# Mechanical.net
KiCad netlist of a schematic drawn in Altium Designer
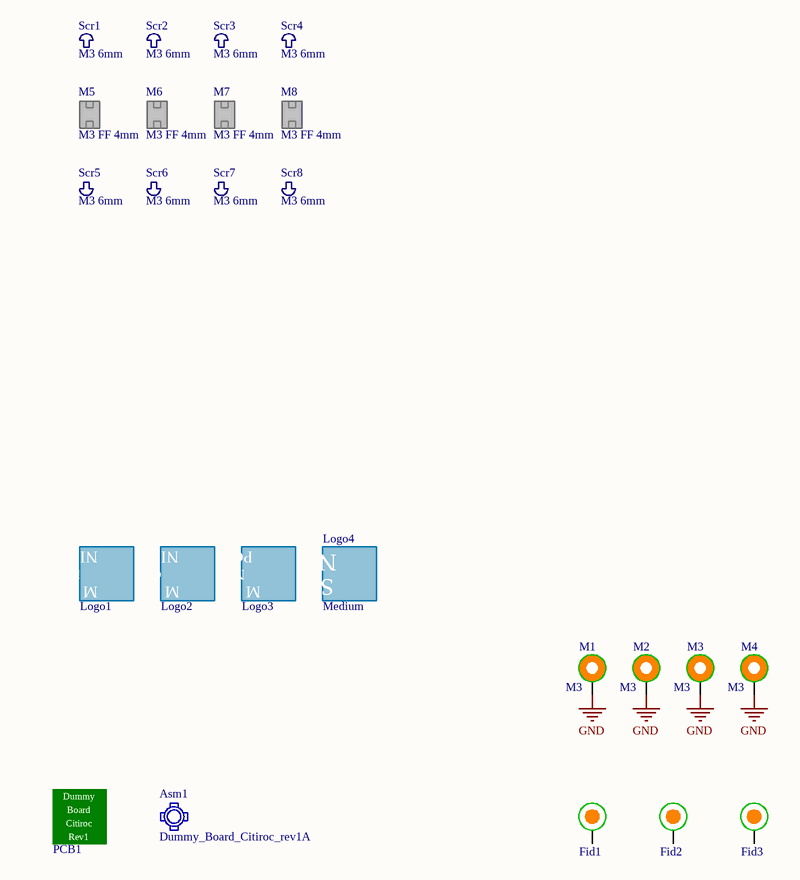
[diagram p0: Mechanical.SchDoc]

(export (version "E")
  (design (tool "Eeschema 10.0.6"))
  (components
    (comp (ref "Asm1")
      (value "Dummy_Board_Citiroc_rev1A")
      (description "Assembly_Dummy_Board_Citiroc_rev1A")
      (libsource (lib "altium-import") (part "root_0_Assembly_Dummy_Board_Citiroc_rev1A_"))
    )
    (comp (ref "Fid1")
      (value "PCB_Fiducial_Round_1mm")
      (footprint "PCB_Fiducial_Round_1mm")
      (libsource (lib "altium-import") (part "root_0_PCB_Fiducial_Round_1mm_"))
    )
    (comp (ref "Fid2")
      (value "PCB_Fiducial_Round_1mm")
      (footprint "PCB_Fiducial_Round_1mm")
      (libsource (lib "altium-import") (part "root_0_PCB_Fiducial_Round_1mm_"))
    )
    (comp (ref "Fid3")
      (value "PCB_Fiducial_Round_1mm")
      (footprint "PCB_Fiducial_Round_1mm")
      (libsource (lib "altium-import") (part "root_0_PCB_Fiducial_Round_1mm_"))
    )
    (comp (ref "Logo1")
      (value "~")
      (footprint "NI_ProjectName_M_Serigraphy")
      (description "NI_ProjectName_M_Serigraphy")
      (libsource (lib "altium-import") (part "root_0_NI_ProjectName_M_Serigraphy_"))
    )
    (comp (ref "Logo2")
      (value "NI_COMPLETE_M_LOGO")
      (footprint "NI_COMPLETE_M_LOGO")
      (libsource (lib "altium-import") (part "root_0_NI_COMPLETE_M_LOGO_"))
    )
    (comp (ref "Logo3")
      (value "PCB_Number_M")
      (footprint "NI_PCB_Number_M_Serigraphy")
      (description "NI_PCB_Number_M_Serigraphy")
      (libsource (lib "altium-import") (part "root_0_NI_PCB_Number_M_Serigraphy_"))
    )
    (comp (ref "Logo4")
      (value "Medium")
      (footprint "NI_SN_MEDIUM")
      (description "NI_SN_MEDIUM")
      (libsource (lib "altium-import") (part "root_0_NI_SN_MEDIUM_"))
    )
    (comp (ref "M1")
      (value "M3")
      (footprint "PCBPad_M3_Head6mm")
      (libsource (lib "altium-import") (part "root_0_PCBPad_M3_Head6mm_"))
    )
    (comp (ref "M2")
      (value "M3")
      (footprint "PCBPad_M3_Head6mm")
      (libsource (lib "altium-import") (part "root_0_PCBPad_M3_Head6mm_"))
    )
    (comp (ref "M3")
      (value "M3")
      (footprint "PCBPad_M3_Head6mm")
      (libsource (lib "altium-import") (part "root_0_PCBPad_M3_Head6mm_"))
    )
    (comp (ref "M4")
      (value "M3")
      (footprint "PCBPad_M3_Head6mm")
      (libsource (lib "altium-import") (part "root_0_PCBPad_M3_Head6mm_"))
    )
    (comp (ref "M5")
      (value "M3 FF 4mm")
      (libsource (lib "altium-import") (part "root_0_Hex_Spacer_R30_M3_FF_4mm_"))
    )
    (comp (ref "M6")
      (value "M3 FF 4mm")
      (libsource (lib "altium-import") (part "root_0_Hex_Spacer_R30_M3_FF_4mm_"))
    )
    (comp (ref "M7")
      (value "M3 FF 4mm")
      (libsource (lib "altium-import") (part "root_0_Hex_Spacer_R30_M3_FF_4mm_"))
    )
    (comp (ref "M8")
      (value "M3 FF 4mm")
      (libsource (lib "altium-import") (part "root_0_Hex_Spacer_R30_M3_FF_4mm_"))
    )
    (comp (ref "PCB1")
      (value "PCB_Dummy_Board_Citiroc_rev1")
      (libsource (lib "altium-import") (part "root_0_PCB_Dummy_Board_Citiroc_rev1_"))
    )
    (comp (ref "Scr1")
      (value "M3 6mm")
      (libsource (lib "altium-import") (part "root_0_Screw_M3_6mm_Pozi_Duratool_"))
    )
    (comp (ref "Scr2")
      (value "M3 6mm")
      (libsource (lib "altium-import") (part "root_0_Screw_M3_6mm_Pozi_Duratool_"))
    )
    (comp (ref "Scr3")
      (value "M3 6mm")
      (libsource (lib "altium-import") (part "root_0_Screw_M3_6mm_Pozi_Duratool_"))
    )
    (comp (ref "Scr4")
      (value "M3 6mm")
      (libsource (lib "altium-import") (part "root_0_Screw_M3_6mm_Pozi_Duratool_"))
    )
    (comp (ref "Scr5")
      (value "M3 6mm")
      (libsource (lib "altium-import") (part "root_2_mirrored_Screw_M3_6mm_Pozi_Duratool_"))
    )
    (comp (ref "Scr6")
      (value "M3 6mm")
      (libsource (lib "altium-import") (part "root_2_mirrored_Screw_M3_6mm_Pozi_Duratool_"))
    )
    (comp (ref "Scr7")
      (value "M3 6mm")
      (libsource (lib "altium-import") (part "root_2_mirrored_Screw_M3_6mm_Pozi_Duratool_"))
    )
    (comp (ref "Scr8")
      (value "M3 6mm")
      (libsource (lib "altium-import") (part "root_2_mirrored_Screw_M3_6mm_Pozi_Duratool_"))
    )
  )
  (nets
    (net (code "1") (name "GND") (class "Default")
      (node (ref "M1") (pin "1") (pinfunction "1_1") (pintype "passive"))
      (node (ref "M2") (pin "1") (pinfunction "1_1") (pintype "passive"))
      (node (ref "M3") (pin "1") (pinfunction "1_1") (pintype "passive"))
      (node (ref "M4") (pin "1") (pinfunction "1_1") (pintype "passive"))
    )
    (net (code "2") (name "unconnected-(Fid1-Pad1)") (class "Default")
      (node (ref "Fid1") (pin "1") (pinfunction "1_1") (pintype "passive"))
    )
    (net (code "3") (name "unconnected-(Fid2-Pad1)") (class "Default")
      (node (ref "Fid2") (pin "1") (pinfunction "1_1") (pintype "passive"))
    )
    (net (code "4") (name "unconnected-(Fid3-Pad1)") (class "Default")
      (node (ref "Fid3") (pin "1") (pinfunction "1_1") (pintype "passive"))
    )
  )
)
